# rev_C.net
KiCad netlist of a schematic drawn in EAGLE
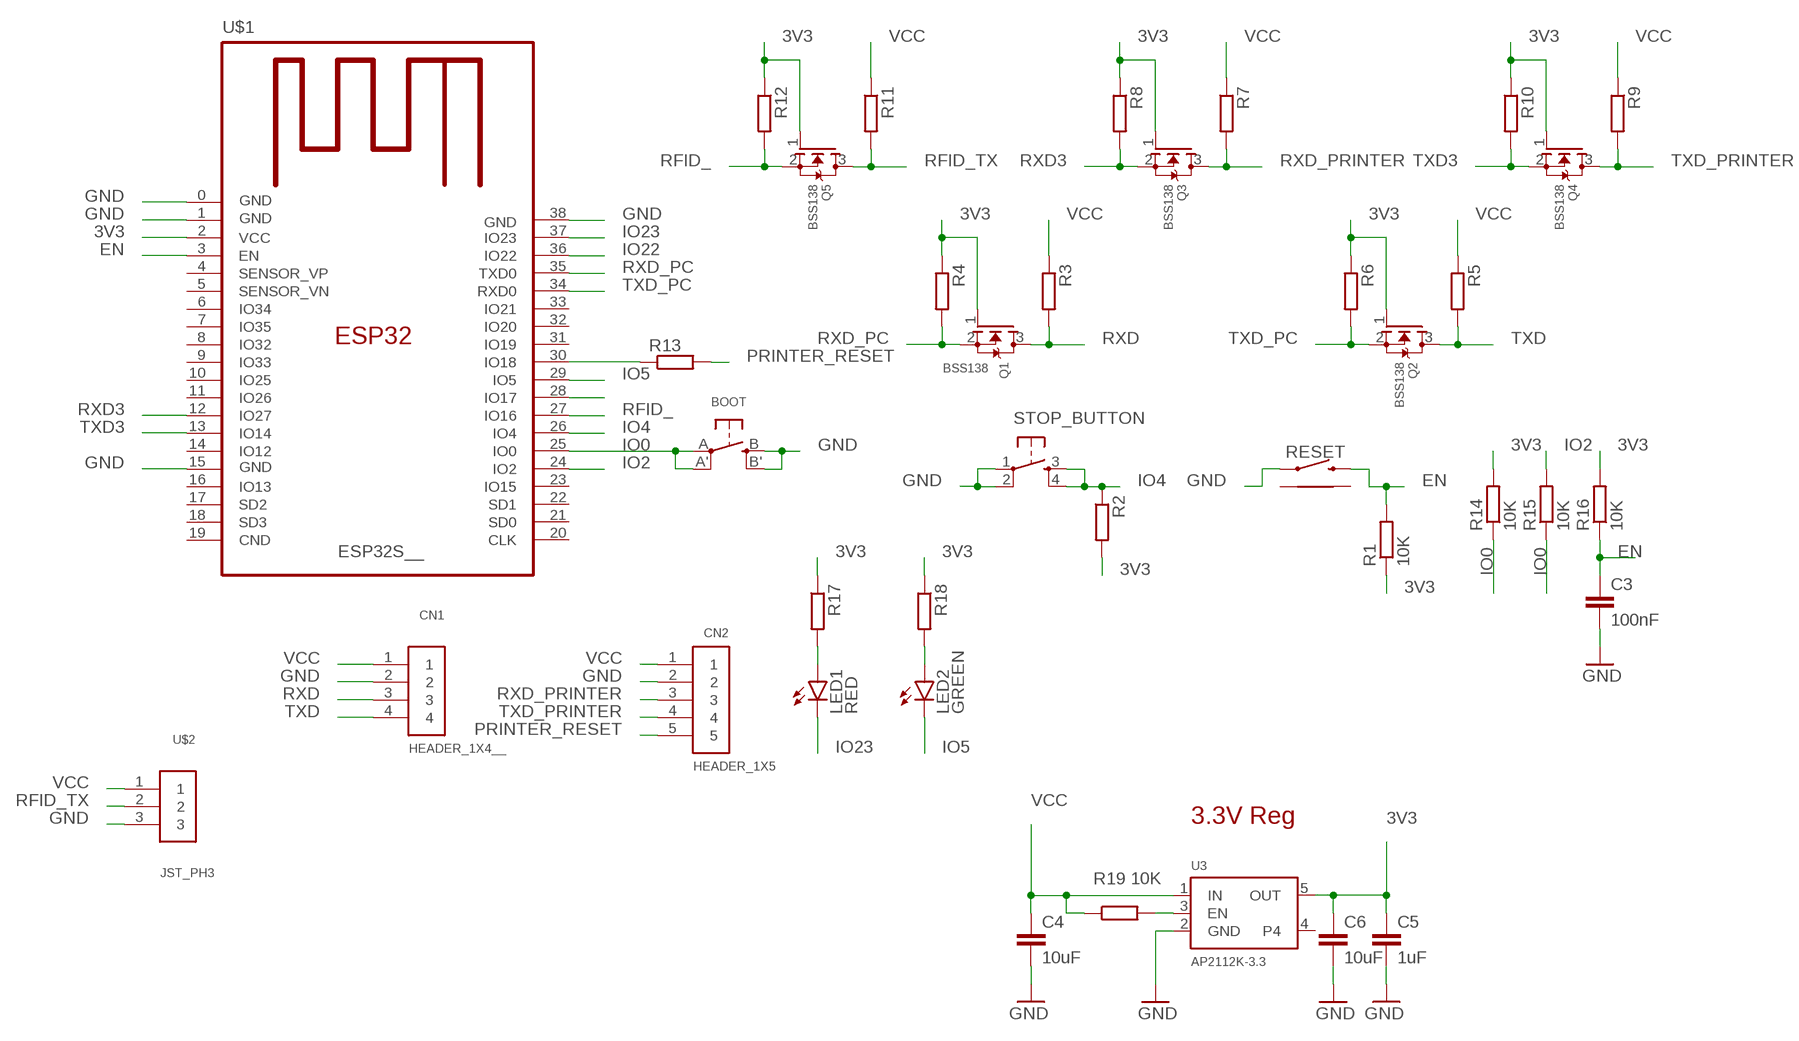
[diagram p0: schematic, sheet 1]

(export (version "E")
  (design (tool "Eeschema 10.0.6"))
  (components
    (comp (ref "BOOT")
      (value "BUTTON_KMR2_4.6X2.8")
      (footprint "eagle-import:BUTTON_KMR2_4.6X2.8")
      (libsource (lib "eagle-import") (part "BUTTON_KMR2_4.6X2.8"))
    )
    (comp (ref "C3")
      (value "100nF")
      (footprint "eagle-import:C0805")
      (libsource (lib "eagle-import") (part "C-EUC0805"))
    )
    (comp (ref "C4")
      (value "10uF")
      (footprint "eagle-import:C0805")
      (libsource (lib "eagle-import") (part "C-EUC0805"))
    )
    (comp (ref "C5")
      (value "1uF")
      (footprint "eagle-import:C0805")
      (libsource (lib "eagle-import") (part "C-EUC0805"))
    )
    (comp (ref "C6")
      (value "10uF")
      (footprint "eagle-import:C0805")
      (libsource (lib "eagle-import") (part "C-EUC0805"))
    )
    (comp (ref "CN1")
      (value "HEADER_1X4__")
      (footprint "eagle-import:HEADER_1X4_RIGHT_ANGLE")
      (libsource (lib "eagle-import") (part "HEADER_1X4__"))
    )
    (comp (ref "CN2")
      (value "HEADER_1X5")
      (footprint "eagle-import:HEADER_1X5")
      (libsource (lib "eagle-import") (part "HEADER_1X5"))
    )
    (comp (ref "LED1")
      (value "RED")
      (footprint "eagle-import:CHIP-LED0805")
      (libsource (lib "eagle-import") (part "LEDCHIP-LED0805"))
    )
    (comp (ref "LED2")
      (value "GREEN")
      (footprint "eagle-import:CHIP-LED0805")
      (libsource (lib "eagle-import") (part "LEDCHIP-LED0805"))
    )
    (comp (ref "Q1")
      (value "BSS138")
      (footprint "eagle-import:SOT95P240X110-3")
      (libsource (lib "eagle-import") (part "MOSFET_N_"))
    )
    (comp (ref "Q2")
      (value "BSS138")
      (footprint "eagle-import:SOT95P240X110-3")
      (libsource (lib "eagle-import") (part "MOSFET_N_"))
    )
    (comp (ref "Q3")
      (value "BSS138")
      (footprint "eagle-import:SOT95P240X110-3")
      (libsource (lib "eagle-import") (part "MOSFET_N_"))
    )
    (comp (ref "Q4")
      (value "BSS138")
      (footprint "eagle-import:SOT95P240X110-3")
      (libsource (lib "eagle-import") (part "MOSFET_N_"))
    )
    (comp (ref "Q5")
      (value "BSS138")
      (footprint "eagle-import:SOT95P240X110-3")
      (libsource (lib "eagle-import") (part "MOSFET_N_"))
    )
    (comp (ref "R1")
      (value "10K")
      (footprint "eagle-import:R0805")
      (libsource (lib "eagle-import") (part "R-EU_R0805"))
    )
    (comp (ref "R2")
      (value "10K")
      (footprint "eagle-import:R0805")
      (libsource (lib "eagle-import") (part "R-EU_R0805"))
    )
    (comp (ref "R3")
      (value "10K")
      (footprint "eagle-import:R0805")
      (libsource (lib "eagle-import") (part "R-EU_R0805"))
    )
    (comp (ref "R4")
      (value "10K")
      (footprint "eagle-import:R0805")
      (libsource (lib "eagle-import") (part "R-EU_R0805"))
    )
    (comp (ref "R5")
      (value "10K")
      (footprint "eagle-import:R0805")
      (libsource (lib "eagle-import") (part "R-EU_R0805"))
    )
    (comp (ref "R6")
      (value "10K")
      (footprint "eagle-import:R0805")
      (libsource (lib "eagle-import") (part "R-EU_R0805"))
    )
    (comp (ref "R7")
      (value "10K")
      (footprint "eagle-import:R0805")
      (libsource (lib "eagle-import") (part "R-EU_R0805"))
    )
    (comp (ref "R8")
      (value "10K")
      (footprint "eagle-import:R0805")
      (libsource (lib "eagle-import") (part "R-EU_R0805"))
    )
    (comp (ref "R9")
      (value "10K")
      (footprint "eagle-import:R0805")
      (libsource (lib "eagle-import") (part "R-EU_R0805"))
    )
    (comp (ref "R10")
      (value "10K")
      (footprint "eagle-import:R0805")
      (libsource (lib "eagle-import") (part "R-EU_R0805"))
    )
    (comp (ref "R11")
      (value "10K")
      (footprint "eagle-import:R0805")
      (libsource (lib "eagle-import") (part "R-EU_R0805"))
    )
    (comp (ref "R12")
      (value "10K")
      (footprint "eagle-import:R0805")
      (libsource (lib "eagle-import") (part "R-EU_R0805"))
    )
    (comp (ref "R13")
      (value "10K")
      (footprint "eagle-import:R0805")
      (libsource (lib "eagle-import") (part "R-EU_R0805"))
    )
    (comp (ref "R14")
      (value "10K")
      (footprint "eagle-import:R0805")
      (libsource (lib "eagle-import") (part "R-EU_R0805"))
    )
    (comp (ref "R15")
      (value "10K")
      (footprint "eagle-import:R0805")
      (libsource (lib "eagle-import") (part "R-EU_R0805"))
    )
    (comp (ref "R16")
      (value "10K")
      (footprint "eagle-import:R0805")
      (libsource (lib "eagle-import") (part "R-EU_R0805"))
    )
    (comp (ref "R17")
      (value "470R")
      (footprint "eagle-import:R0805")
      (libsource (lib "eagle-import") (part "R-EU_R0805"))
    )
    (comp (ref "R18")
      (value "470R")
      (footprint "eagle-import:R0805")
      (libsource (lib "eagle-import") (part "R-EU_R0805"))
    )
    (comp (ref "R19")
      (value "10K")
      (footprint "eagle-import:R0805")
      (libsource (lib "eagle-import") (part "R-EU_R0805"))
    )
    (comp (ref "RESET")
      (value "TACTILE_SWITCH_RIGHT_ANGLE_THT_")
      (footprint "eagle-import:TACTILE_SWITCH_RIGHT_ANGLE_THT")
      (libsource (lib "eagle-import") (part "TACTILE_SWITCH_RIGHT_ANGLE_THT_"))
    )
    (comp (ref "STOP_BUTTON")
      (value "TACTILE_SWITCH_LONG_THT_")
      (footprint "eagle-import:TACTILE_SWICTH_THT")
      (libsource (lib "eagle-import") (part "TACTILE_SWITCH_LONG_THT_"))
    )
    (comp (ref "U$1")
      (value "ESP32S__")
      (footprint "eagle-import:ESP32S")
      (libsource (lib "eagle-import") (part "ESP32S__"))
    )
    (comp (ref "U$2")
      (value "JST_PH3")
      (footprint "eagle-import:JST-PH3")
      (libsource (lib "eagle-import") (part "JST_PH3"))
    )
    (comp (ref "U3")
      (value "AP2112K-3.3")
      (footprint "eagle-import:SOT95P290X120-5")
      (libsource (lib "eagle-import") (part "AP2112K-3.3_"))
    )
  )
  (nets
    (net (code "1") (name "/3V3") (class "Default")
      (node (ref "C5") (pin "1") (pinfunction "1_1") (pintype "passive"))
      (node (ref "C6") (pin "1") (pinfunction "1_1") (pintype "passive"))
      (node (ref "Q1") (pin "1") (pinfunction "G_1") (pintype "bidirectional"))
      (node (ref "Q2") (pin "1") (pinfunction "G_1") (pintype "bidirectional"))
      (node (ref "Q3") (pin "1") (pinfunction "G_1") (pintype "bidirectional"))
      (node (ref "Q4") (pin "1") (pinfunction "G_1") (pintype "bidirectional"))
      (node (ref "Q5") (pin "1") (pinfunction "G_1") (pintype "bidirectional"))
      (node (ref "R1") (pin "1") (pinfunction "1_1") (pintype "passive"))
      (node (ref "R10") (pin "1") (pinfunction "1_1") (pintype "passive"))
      (node (ref "R12") (pin "1") (pinfunction "1_1") (pintype "passive"))
      (node (ref "R14") (pin "2") (pinfunction "2_2") (pintype "passive"))
      (node (ref "R16") (pin "2") (pinfunction "2_2") (pintype "passive"))
      (node (ref "R17") (pin "1") (pinfunction "1_1") (pintype "passive"))
      (node (ref "R18") (pin "1") (pinfunction "1_1") (pintype "passive"))
      (node (ref "R2") (pin "2") (pinfunction "2_2") (pintype "passive"))
      (node (ref "R4") (pin "1") (pinfunction "1_1") (pintype "passive"))
      (node (ref "R6") (pin "1") (pinfunction "1_1") (pintype "passive"))
      (node (ref "R8") (pin "1") (pinfunction "1_1") (pintype "passive"))
      (node (ref "U$1") (pin "2") (pinfunction "VCC_2") (pintype "power_in"))
      (node (ref "U3") (pin "5") (pinfunction "OUT_5") (pintype "bidirectional"))
    )
    (net (code "2") (name "/EN") (class "Default")
      (node (ref "C3") (pin "1") (pinfunction "1_1") (pintype "passive"))
      (node (ref "R1") (pin "2") (pinfunction "2_2") (pintype "passive"))
      (node (ref "R16") (pin "1") (pinfunction "1_1") (pintype "passive"))
      (node (ref "RESET") (pin "2") (pinfunction "2_2") (pintype "passive"))
      (node (ref "U$1") (pin "3") (pinfunction "EN_3") (pintype "bidirectional"))
    )
    (net (code "3") (name "/IO0") (class "Default")
      (node (ref "BOOT") (pin "A") (pinfunction "P_A") (pintype "passive"))
      (node (ref "BOOT") (pin "A'") (pinfunction "P1_A'") (pintype "passive"))
      (node (ref "R14") (pin "1") (pinfunction "1_1") (pintype "passive"))
      (node (ref "R15") (pin "1") (pinfunction "1_1") (pintype "passive"))
      (node (ref "U$1") (pin "25") (pinfunction "IO0_25") (pintype "bidirectional"))
    )
    (net (code "4") (name "/IO2") (class "Default")
      (node (ref "R15") (pin "2") (pinfunction "2_2") (pintype "passive"))
      (node (ref "U$1") (pin "24") (pinfunction "IO2_24") (pintype "bidirectional"))
    )
    (net (code "5") (name "/IO4") (class "Default")
      (node (ref "R2") (pin "1") (pinfunction "1_1") (pintype "passive"))
      (node (ref "STOP_BUTTON") (pin "3") (pinfunction "3_3") (pintype "passive"))
      (node (ref "STOP_BUTTON") (pin "4") (pinfunction "4_4") (pintype "passive"))
      (node (ref "U$1") (pin "26") (pinfunction "IO4_26") (pintype "bidirectional"))
    )
    (net (code "6") (name "/IO5") (class "Default")
      (node (ref "LED2") (pin "C") (pinfunction "C_C") (pintype "passive"))
      (node (ref "U$1") (pin "29") (pinfunction "IO5_29") (pintype "bidirectional"))
    )
    (net (code "7") (name "/IO22") (class "Default")
      (node (ref "U$1") (pin "36") (pinfunction "IO22_36") (pintype "bidirectional"))
    )
    (net (code "8") (name "/IO23") (class "Default")
      (node (ref "LED1") (pin "C") (pinfunction "C_C") (pintype "passive"))
      (node (ref "U$1") (pin "37") (pinfunction "IO23_37") (pintype "bidirectional"))
    )
    (net (code "9") (name "/PRINTER_RESET") (class "Default")
      (node (ref "CN2") (pin "5") (pinfunction "5_5") (pintype "bidirectional"))
      (node (ref "R13") (pin "2") (pinfunction "2_2") (pintype "passive"))
    )
    (net (code "10") (name "/RFID_") (class "Default")
      (node (ref "Q5") (pin "2") (pinfunction "S_2") (pintype "bidirectional"))
      (node (ref "R12") (pin "2") (pinfunction "2_2") (pintype "passive"))
      (node (ref "U$1") (pin "27") (pinfunction "IO16_27") (pintype "bidirectional"))
    )
    (net (code "11") (name "/RFID_TX") (class "Default")
      (node (ref "Q5") (pin "3") (pinfunction "D_3") (pintype "bidirectional"))
      (node (ref "R11") (pin "2") (pinfunction "2_2") (pintype "passive"))
      (node (ref "U$2") (pin "2") (pinfunction "2_2") (pintype "bidirectional"))
    )
    (net (code "12") (name "/RXD") (class "Default")
      (node (ref "CN1") (pin "3") (pinfunction "3_3") (pintype "bidirectional"))
      (node (ref "Q1") (pin "3") (pinfunction "D_3") (pintype "bidirectional"))
      (node (ref "R3") (pin "2") (pinfunction "2_2") (pintype "passive"))
    )
    (net (code "13") (name "/RXD3") (class "Default")
      (node (ref "Q3") (pin "2") (pinfunction "S_2") (pintype "bidirectional"))
      (node (ref "R8") (pin "2") (pinfunction "2_2") (pintype "passive"))
      (node (ref "U$1") (pin "12") (pinfunction "IO27_12") (pintype "bidirectional"))
    )
    (net (code "14") (name "/RXD_PC") (class "Default")
      (node (ref "Q1") (pin "2") (pinfunction "S_2") (pintype "bidirectional"))
      (node (ref "R4") (pin "2") (pinfunction "2_2") (pintype "passive"))
      (node (ref "U$1") (pin "35") (pinfunction "TXD0_35") (pintype "bidirectional"))
    )
    (net (code "15") (name "/RXD_PRINTER") (class "Default")
      (node (ref "CN2") (pin "3") (pinfunction "3_3") (pintype "bidirectional"))
      (node (ref "Q3") (pin "3") (pinfunction "D_3") (pintype "bidirectional"))
      (node (ref "R7") (pin "2") (pinfunction "2_2") (pintype "passive"))
    )
    (net (code "16") (name "/TXD") (class "Default")
      (node (ref "CN1") (pin "4") (pinfunction "4_4") (pintype "bidirectional"))
      (node (ref "Q2") (pin "3") (pinfunction "D_3") (pintype "bidirectional"))
      (node (ref "R5") (pin "2") (pinfunction "2_2") (pintype "passive"))
    )
    (net (code "17") (name "/TXD3") (class "Default")
      (node (ref "Q4") (pin "2") (pinfunction "S_2") (pintype "bidirectional"))
      (node (ref "R10") (pin "2") (pinfunction "2_2") (pintype "passive"))
      (node (ref "U$1") (pin "13") (pinfunction "IO14_13") (pintype "bidirectional"))
    )
    (net (code "18") (name "/TXD_PC") (class "Default")
      (node (ref "Q2") (pin "2") (pinfunction "S_2") (pintype "bidirectional"))
      (node (ref "R6") (pin "2") (pinfunction "2_2") (pintype "passive"))
      (node (ref "U$1") (pin "34") (pinfunction "RXD0_34") (pintype "bidirectional"))
    )
    (net (code "19") (name "/TXD_PRINTER") (class "Default")
      (node (ref "CN2") (pin "4") (pinfunction "4_4") (pintype "bidirectional"))
      (node (ref "Q4") (pin "3") (pinfunction "D_3") (pintype "bidirectional"))
      (node (ref "R9") (pin "2") (pinfunction "2_2") (pintype "passive"))
    )
    (net (code "20") (name "/VCC") (class "Default")
      (node (ref "C4") (pin "1") (pinfunction "1_1") (pintype "passive"))
      (node (ref "CN1") (pin "1") (pinfunction "1_1") (pintype "bidirectional"))
      (node (ref "CN2") (pin "1") (pinfunction "1_1") (pintype "bidirectional"))
      (node (ref "R11") (pin "1") (pinfunction "1_1") (pintype "passive"))
      (node (ref "R19") (pin "1") (pinfunction "1_1") (pintype "passive"))
      (node (ref "R3") (pin "1") (pinfunction "1_1") (pintype "passive"))
      (node (ref "R5") (pin "1") (pinfunction "1_1") (pintype "passive"))
      (node (ref "R7") (pin "1") (pinfunction "1_1") (pintype "passive"))
      (node (ref "R9") (pin "1") (pinfunction "1_1") (pintype "passive"))
      (node (ref "U$2") (pin "1") (pinfunction "1_1") (pintype "bidirectional"))
      (node (ref "U3") (pin "1") (pinfunction "IN_1") (pintype "bidirectional"))
    )
    (net (code "21") (name "GND") (class "Default")
      (node (ref "BOOT") (pin "B") (pinfunction "S_B") (pintype "passive"))
      (node (ref "BOOT") (pin "B'") (pinfunction "S1_B'") (pintype "passive"))
      (node (ref "C3") (pin "2") (pinfunction "2_2") (pintype "passive"))
      (node (ref "C4") (pin "2") (pinfunction "2_2") (pintype "passive"))
      (node (ref "C5") (pin "2") (pinfunction "2_2") (pintype "passive"))
      (node (ref "C6") (pin "2") (pinfunction "2_2") (pintype "passive"))
      (node (ref "CN1") (pin "2") (pinfunction "2_2") (pintype "bidirectional"))
      (node (ref "CN2") (pin "2") (pinfunction "2_2") (pintype "bidirectional"))
      (node (ref "RESET") (pin "1") (pinfunction "1_1") (pintype "passive"))
      (node (ref "STOP_BUTTON") (pin "1") (pinfunction "1_1") (pintype "passive"))
      (node (ref "STOP_BUTTON") (pin "2") (pinfunction "2_2") (pintype "passive"))
      (node (ref "U$1") (pin "0") (pinfunction "GND_0") (pintype "power_in"))
      (node (ref "U$1") (pin "1") (pinfunction "GND_1") (pintype "power_in"))
      (node (ref "U$1") (pin "15") (pinfunction "GND_15") (pintype "power_in"))
      (node (ref "U$1") (pin "38") (pinfunction "GND_38") (pintype "power_in"))
      (node (ref "U$2") (pin "3") (pinfunction "3_3") (pintype "bidirectional"))
      (node (ref "U3") (pin "2") (pinfunction "GND_2") (pintype "bidirectional"))
    )
    (net (code "22") (name "Net-(LED1-PadA)") (class "Default")
      (node (ref "LED1") (pin "A") (pinfunction "A_A") (pintype "passive"))
      (node (ref "R17") (pin "2") (pinfunction "2_2") (pintype "passive"))
    )
    (net (code "23") (name "Net-(LED2-PadA)") (class "Default")
      (node (ref "LED2") (pin "A") (pinfunction "A_A") (pintype "passive"))
      (node (ref "R18") (pin "2") (pinfunction "2_2") (pintype "passive"))
    )
    (net (code "24") (name "Net-(U$1-IO18)") (class "Default")
      (node (ref "R13") (pin "1") (pinfunction "1_1") (pintype "passive"))
      (node (ref "U$1") (pin "30") (pinfunction "IO18_30") (pintype "bidirectional"))
    )
    (net (code "25") (name "Net-(U3-EN)") (class "Default")
      (node (ref "R19") (pin "2") (pinfunction "2_2") (pintype "passive"))
      (node (ref "U3") (pin "3") (pinfunction "EN_3") (pintype "bidirectional"))
    )
    (net (code "26") (name "unconnected-(RESET-3-PadANCHOR1)") (class "Default")
      (node (ref "RESET") (pin "ANCHOR1") (pinfunction "3_ANCHOR1") (pintype "passive"))
    )
    (net (code "27") (name "unconnected-(RESET-4-PadANCHOR2)") (class "Default")
      (node (ref "RESET") (pin "ANCHOR2") (pinfunction "4_ANCHOR2") (pintype "passive"))
    )
    (net (code "28") (name "unconnected-(U$1-CLK-Pad20)") (class "Default")
      (node (ref "U$1") (pin "20") (pinfunction "CLK_20") (pintype "bidirectional"))
    )
    (net (code "29") (name "unconnected-(U$1-CND-Pad19)") (class "Default")
      (node (ref "U$1") (pin "19") (pinfunction "CND_19") (pintype "bidirectional"))
    )
    (net (code "30") (name "unconnected-(U$1-IO12-Pad14)") (class "Default")
      (node (ref "U$1") (pin "14") (pinfunction "IO12_14") (pintype "bidirectional"))
    )
    (net (code "31") (name "unconnected-(U$1-IO13-Pad16)") (class "Default")
      (node (ref "U$1") (pin "16") (pinfunction "IO13_16") (pintype "bidirectional"))
    )
    (net (code "32") (name "unconnected-(U$1-IO15-Pad23)") (class "Default")
      (node (ref "U$1") (pin "23") (pinfunction "IO15_23") (pintype "bidirectional"))
    )
    (net (code "33") (name "unconnected-(U$1-IO17-Pad28)") (class "Default")
      (node (ref "U$1") (pin "28") (pinfunction "IO17_28") (pintype "bidirectional"))
    )
    (net (code "34") (name "unconnected-(U$1-IO19-Pad31)") (class "Default")
      (node (ref "U$1") (pin "31") (pinfunction "IO19_31") (pintype "bidirectional"))
    )
    (net (code "35") (name "unconnected-(U$1-IO20-Pad32)") (class "Default")
      (node (ref "U$1") (pin "32") (pinfunction "IO20_32") (pintype "bidirectional"))
    )
    (net (code "36") (name "unconnected-(U$1-IO21-Pad33)") (class "Default")
      (node (ref "U$1") (pin "33") (pinfunction "IO21_33") (pintype "bidirectional"))
    )
    (net (code "37") (name "unconnected-(U$1-IO25-Pad10)") (class "Default")
      (node (ref "U$1") (pin "10") (pinfunction "IO25_10") (pintype "bidirectional"))
    )
    (net (code "38") (name "unconnected-(U$1-IO26-Pad11)") (class "Default")
      (node (ref "U$1") (pin "11") (pinfunction "IO26_11") (pintype "bidirectional"))
    )
    (net (code "39") (name "unconnected-(U$1-IO32-Pad8)") (class "Default")
      (node (ref "U$1") (pin "8") (pinfunction "IO32_8") (pintype "bidirectional"))
    )
    (net (code "40") (name "unconnected-(U$1-IO33-Pad9)") (class "Default")
      (node (ref "U$1") (pin "9") (pinfunction "IO33_9") (pintype "bidirectional"))
    )
    (net (code "41") (name "unconnected-(U$1-IO34-Pad6)") (class "Default")
      (node (ref "U$1") (pin "6") (pinfunction "IO34_6") (pintype "bidirectional"))
    )
    (net (code "42") (name "unconnected-(U$1-IO35-Pad7)") (class "Default")
      (node (ref "U$1") (pin "7") (pinfunction "IO35_7") (pintype "bidirectional"))
    )
    (net (code "43") (name "unconnected-(U$1-SD0-Pad21)") (class "Default")
      (node (ref "U$1") (pin "21") (pinfunction "SD0_21") (pintype "bidirectional"))
    )
    (net (code "44") (name "unconnected-(U$1-SD1-Pad22)") (class "Default")
      (node (ref "U$1") (pin "22") (pinfunction "SD1_22") (pintype "bidirectional"))
    )
    (net (code "45") (name "unconnected-(U$1-SD2-Pad17)") (class "Default")
      (node (ref "U$1") (pin "17") (pinfunction "SD2_17") (pintype "bidirectional"))
    )
    (net (code "46") (name "unconnected-(U$1-SD3-Pad18)") (class "Default")
      (node (ref "U$1") (pin "18") (pinfunction "SD3_18") (pintype "bidirectional"))
    )
    (net (code "47") (name "unconnected-(U$1-SENSOR_VN-Pad5)") (class "Default")
      (node (ref "U$1") (pin "5") (pinfunction "SENSOR_VN_5") (pintype "bidirectional"))
    )
    (net (code "48") (name "unconnected-(U$1-SENSOR_VP-Pad4)") (class "Default")
      (node (ref "U$1") (pin "4") (pinfunction "SENSOR_VP_4") (pintype "bidirectional"))
    )
    (net (code "49") (name "unconnected-(U3-P4-Pad4)") (class "Default")
      (node (ref "U3") (pin "4") (pinfunction "P4_4") (pintype "bidirectional"))
    )
  )
)
